# PC3_Output.net
KiCad netlist of a schematic drawn in Altium Designer
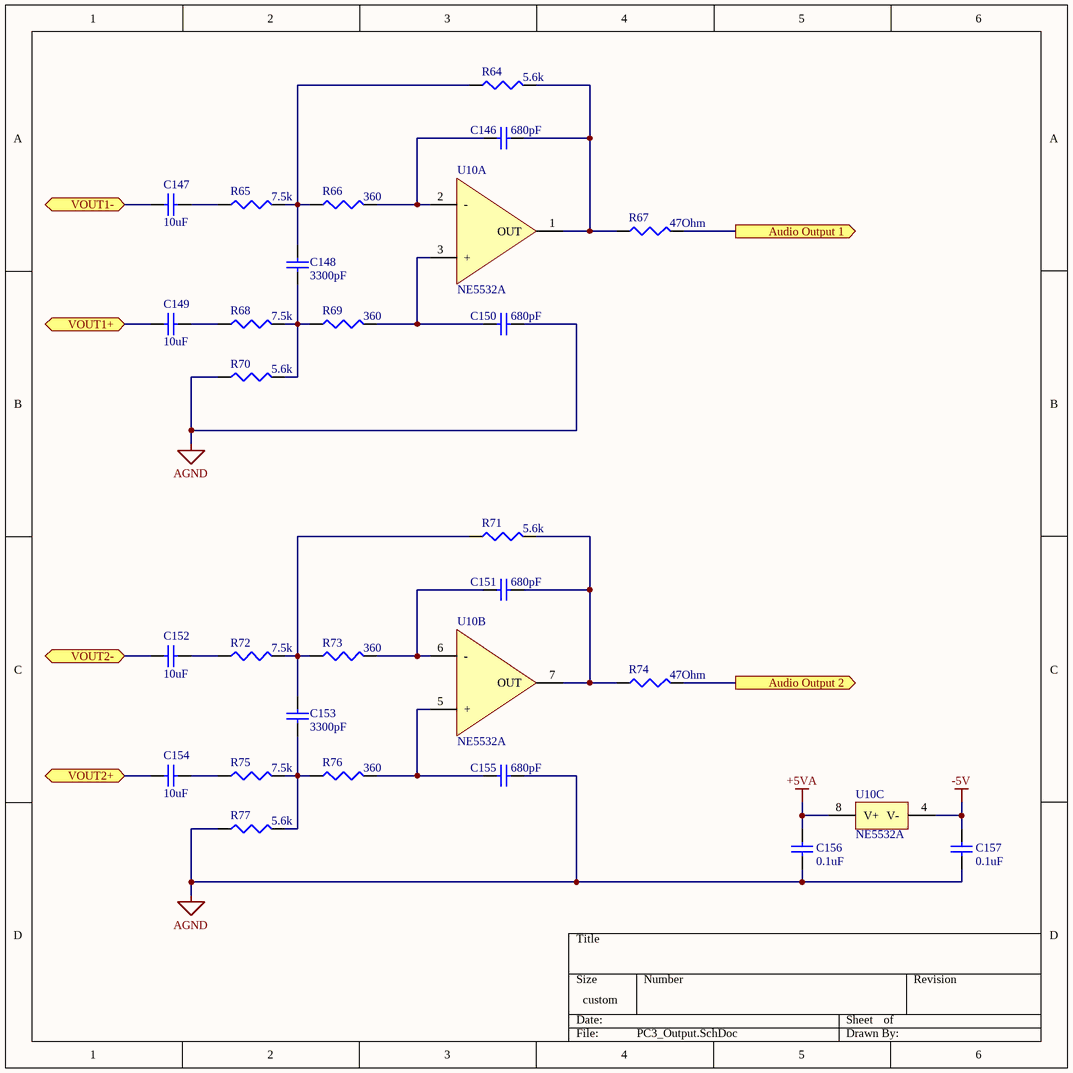
[diagram p0: PC3_Output.SchDoc]

(export (version "E")
  (design (tool "Eeschema 10.0.6"))
  (components
    (comp (ref "C146")
      (value "680pF")
      (footprint "CAPC1608X08")
      (description "Capacitor (Semiconductor SIM Model)")
      (fields (field (name "Comment") "Cap Semi"))
      (libsource (lib "Michel") (part "Cap Semi"))
    )
    (comp (ref "C147")
      (value "10uF")
      (footprint "CAPC1608X08")
      (description "Capacitor (Semiconductor SIM Model)")
      (libsource (lib "Michel") (part "Cap Semi"))
    )
    (comp (ref "C148")
      (value "3300pF")
      (footprint "CAPC1608X08")
      (description "Capacitor (Semiconductor SIM Model)")
      (fields (field (name "Comment") "Cap Semi"))
      (libsource (lib "Michel") (part "Cap Semi"))
    )
    (comp (ref "C149")
      (value "10uF")
      (footprint "CAPC1608X08")
      (description "Capacitor (Semiconductor SIM Model)")
      (libsource (lib "Michel") (part "Cap Semi"))
    )
    (comp (ref "C150")
      (value "680pF")
      (footprint "CAPC1608X08")
      (description "Capacitor (Semiconductor SIM Model)")
      (fields (field (name "Comment") "Cap Semi"))
      (libsource (lib "Michel") (part "Cap Semi"))
    )
    (comp (ref "C151")
      (value "680pF")
      (footprint "CAPC1608X08")
      (description "Capacitor (Semiconductor SIM Model)")
      (fields (field (name "Comment") "Cap Semi"))
      (libsource (lib "Michel") (part "Cap Semi"))
    )
    (comp (ref "C152")
      (value "10uF")
      (footprint "CAPC1608X08")
      (description "Capacitor (Semiconductor SIM Model)")
      (libsource (lib "Michel") (part "Cap Semi"))
    )
    (comp (ref "C153")
      (value "3300pF")
      (footprint "CAPC1608X08")
      (description "Capacitor (Semiconductor SIM Model)")
      (fields (field (name "Comment") "Cap Semi"))
      (libsource (lib "Michel") (part "Cap Semi"))
    )
    (comp (ref "C154")
      (value "10uF")
      (footprint "CAPC1608X08")
      (description "Capacitor (Semiconductor SIM Model)")
      (libsource (lib "Michel") (part "Cap Semi"))
    )
    (comp (ref "C155")
      (value "680pF")
      (footprint "CAPC1608X08")
      (description "Capacitor (Semiconductor SIM Model)")
      (fields (field (name "Comment") "Cap Semi"))
      (libsource (lib "Michel") (part "Cap Semi"))
    )
    (comp (ref "C156")
      (value "0.1uF")
      (footprint "CAPC1608X08")
      (description "Capacitor (Semiconductor SIM Model)")
      (libsource (lib "Michel") (part "Cap Semi"))
    )
    (comp (ref "C157")
      (value "0.1uF")
      (footprint "CAPC1608X08")
      (description "Capacitor (Semiconductor SIM Model)")
      (libsource (lib "Michel") (part "Cap Semi"))
    )
    (comp (ref "R64")
      (value "5.6k")
      (footprint "RESC1608X05")
      (description "Resistor")
      (fields (field (name "Comment") "Res3"))
      (libsource (lib "Michel") (part "Res3"))
    )
    (comp (ref "R65")
      (value "7.5k")
      (footprint "RESC1608X05")
      (description "Resistor")
      (fields (field (name "Comment") "Res3"))
      (libsource (lib "Michel") (part "Res3"))
    )
    (comp (ref "R66")
      (value "360")
      (footprint "RESC1608X05")
      (description "Resistor")
      (fields (field (name "Comment") "Res3"))
      (libsource (lib "Michel") (part "Res3"))
    )
    (comp (ref "R67")
      (value "47Ohm")
      (footprint "RESC1608X05")
      (description "Resistor")
      (fields (field (name "Comment") "Res3"))
      (libsource (lib "Michel") (part "Res3"))
    )
    (comp (ref "R68")
      (value "7.5k")
      (footprint "RESC1608X05")
      (description "Resistor")
      (fields (field (name "Comment") "Res3"))
      (libsource (lib "Michel") (part "Res3"))
    )
    (comp (ref "R69")
      (value "360")
      (footprint "RESC1608X05")
      (description "Resistor")
      (fields (field (name "Comment") "Res3"))
      (libsource (lib "Michel") (part "Res3"))
    )
    (comp (ref "R70")
      (value "5.6k")
      (footprint "RESC1608X05")
      (description "Resistor")
      (fields (field (name "Comment") "Res3"))
      (libsource (lib "Michel") (part "Res3"))
    )
    (comp (ref "R71")
      (value "5.6k")
      (footprint "RESC1608X05")
      (description "Resistor")
      (fields (field (name "Comment") "Res3"))
      (libsource (lib "Michel") (part "Res3"))
    )
    (comp (ref "R72")
      (value "7.5k")
      (footprint "RESC1608X05")
      (description "Resistor")
      (fields (field (name "Comment") "Res3"))
      (libsource (lib "Michel") (part "Res3"))
    )
    (comp (ref "R73")
      (value "360")
      (footprint "RESC1608X05")
      (description "Resistor")
      (fields (field (name "Comment") "Res3"))
      (libsource (lib "Michel") (part "Res3"))
    )
    (comp (ref "R74")
      (value "47Ohm")
      (footprint "RESC1608X05")
      (description "Resistor")
      (fields (field (name "Comment") "Res3"))
      (libsource (lib "Michel") (part "Res3"))
    )
    (comp (ref "R75")
      (value "7.5k")
      (footprint "RESC1608X05")
      (description "Resistor")
      (fields (field (name "Comment") "Res3"))
      (libsource (lib "Michel") (part "Res3"))
    )
    (comp (ref "R76")
      (value "360")
      (footprint "RESC1608X05")
      (description "Resistor")
      (fields (field (name "Comment") "Res3"))
      (libsource (lib "Michel") (part "Res3"))
    )
    (comp (ref "R77")
      (value "5.6k")
      (footprint "RESC1608X05")
      (description "Resistor")
      (fields (field (name "Comment") "Res3"))
      (libsource (lib "Michel") (part "Res3"))
    )
    (comp (ref "U10")
      (value "NE5532A")
      (footprint "D8-M")
      (description "Amplificateur Opérationnel")
      (libsource (lib "Michel") (part "NE5532A"))
    )
  )
  (nets
    (net (code "1") (name "+5VA") (class "Default")
      (node (ref "C156") (pin "1") (pinfunction "1_1") (pintype "passive"))
      (node (ref "U10") (pin "8") (pinfunction "V+_8") (pintype "passive"))
    )
    (net (code "2") (name "-5V") (class "Default")
      (node (ref "C157") (pin "1") (pinfunction "1_1") (pintype "passive"))
      (node (ref "U10") (pin "4") (pinfunction "V-_4") (pintype "passive"))
    )
    (net (code "3") (name "/Audio Output 1") (class "Default")
      (node (ref "R67") (pin "2") (pinfunction "2_2") (pintype "passive"))
    )
    (net (code "4") (name "/Audio Output 2") (class "Default")
      (node (ref "R74") (pin "2") (pinfunction "2_2") (pintype "passive"))
    )
    (net (code "5") (name "/VOUT1+") (class "Default")
      (node (ref "C149") (pin "2") (pinfunction "2_2") (pintype "passive"))
    )
    (net (code "6") (name "/VOUT1-") (class "Default")
      (node (ref "C147") (pin "2") (pinfunction "2_2") (pintype "passive"))
    )
    (net (code "7") (name "/VOUT2+") (class "Default")
      (node (ref "C154") (pin "2") (pinfunction "2_2") (pintype "passive"))
    )
    (net (code "8") (name "/VOUT2-") (class "Default")
      (node (ref "C152") (pin "2") (pinfunction "2_2") (pintype "passive"))
    )
    (net (code "9") (name "AGND") (class "Default")
      (node (ref "C150") (pin "1") (pinfunction "1_1") (pintype "passive"))
      (node (ref "C155") (pin "1") (pinfunction "1_1") (pintype "passive"))
      (node (ref "C156") (pin "2") (pinfunction "2_2") (pintype "passive"))
      (node (ref "C157") (pin "2") (pinfunction "2_2") (pintype "passive"))
      (node (ref "R70") (pin "1") (pinfunction "1_1") (pintype "passive"))
      (node (ref "R77") (pin "1") (pinfunction "1_1") (pintype "passive"))
    )
    (net (code "10") (name "Net-(C147-Pad1)") (class "Default")
      (node (ref "C147") (pin "1") (pinfunction "1_1") (pintype "passive"))
      (node (ref "R65") (pin "1") (pinfunction "1_1") (pintype "passive"))
    )
    (net (code "11") (name "Net-(C148-Pad1)") (class "Default")
      (node (ref "C148") (pin "1") (pinfunction "1_1") (pintype "passive"))
      (node (ref "R64") (pin "1") (pinfunction "1_1") (pintype "passive"))
      (node (ref "R65") (pin "2") (pinfunction "2_2") (pintype "passive"))
      (node (ref "R66") (pin "1") (pinfunction "1_1") (pintype "passive"))
    )
    (net (code "12") (name "Net-(C148-Pad2)") (class "Default")
      (node (ref "C148") (pin "2") (pinfunction "2_2") (pintype "passive"))
      (node (ref "R68") (pin "2") (pinfunction "2_2") (pintype "passive"))
      (node (ref "R69") (pin "1") (pinfunction "1_1") (pintype "passive"))
      (node (ref "R70") (pin "2") (pinfunction "2_2") (pintype "passive"))
    )
    (net (code "13") (name "Net-(C149-Pad1)") (class "Default")
      (node (ref "C149") (pin "1") (pinfunction "1_1") (pintype "passive"))
      (node (ref "R68") (pin "1") (pinfunction "1_1") (pintype "passive"))
    )
    (net (code "14") (name "Net-(C152-Pad1)") (class "Default")
      (node (ref "C152") (pin "1") (pinfunction "1_1") (pintype "passive"))
      (node (ref "R72") (pin "1") (pinfunction "1_1") (pintype "passive"))
    )
    (net (code "15") (name "Net-(C153-Pad1)") (class "Default")
      (node (ref "C153") (pin "1") (pinfunction "1_1") (pintype "passive"))
      (node (ref "R71") (pin "1") (pinfunction "1_1") (pintype "passive"))
      (node (ref "R72") (pin "2") (pinfunction "2_2") (pintype "passive"))
      (node (ref "R73") (pin "1") (pinfunction "1_1") (pintype "passive"))
    )
    (net (code "16") (name "Net-(C153-Pad2)") (class "Default")
      (node (ref "C153") (pin "2") (pinfunction "2_2") (pintype "passive"))
      (node (ref "R75") (pin "2") (pinfunction "2_2") (pintype "passive"))
      (node (ref "R76") (pin "1") (pinfunction "1_1") (pintype "passive"))
      (node (ref "R77") (pin "2") (pinfunction "2_2") (pintype "passive"))
    )
    (net (code "17") (name "Net-(C154-Pad1)") (class "Default")
      (node (ref "C154") (pin "1") (pinfunction "1_1") (pintype "passive"))
      (node (ref "R75") (pin "1") (pinfunction "1_1") (pintype "passive"))
    )
    (net (code "18") (name "Net-(U10A-+)") (class "Default")
      (node (ref "C150") (pin "2") (pinfunction "2_2") (pintype "passive"))
      (node (ref "R69") (pin "2") (pinfunction "2_2") (pintype "passive"))
      (node (ref "U10") (pin "3") (pinfunction "+_3") (pintype "passive"))
    )
    (net (code "19") (name "Net-(U10A--)") (class "Default")
      (node (ref "C146") (pin "2") (pinfunction "2_2") (pintype "passive"))
      (node (ref "R66") (pin "2") (pinfunction "2_2") (pintype "passive"))
      (node (ref "U10") (pin "2") (pinfunction "-_2") (pintype "passive"))
    )
    (net (code "20") (name "Net-(U10A-OUT)") (class "Default")
      (node (ref "C146") (pin "1") (pinfunction "1_1") (pintype "passive"))
      (node (ref "R64") (pin "2") (pinfunction "2_2") (pintype "passive"))
      (node (ref "R67") (pin "1") (pinfunction "1_1") (pintype "passive"))
      (node (ref "U10") (pin "1") (pinfunction "OUT_1") (pintype "passive"))
    )
    (net (code "21") (name "Net-(U10B-+)") (class "Default")
      (node (ref "C155") (pin "2") (pinfunction "2_2") (pintype "passive"))
      (node (ref "R76") (pin "2") (pinfunction "2_2") (pintype "passive"))
      (node (ref "U10") (pin "5") (pinfunction "+_5") (pintype "passive"))
    )
    (net (code "22") (name "Net-(U10B--)") (class "Default")
      (node (ref "C151") (pin "2") (pinfunction "2_2") (pintype "passive"))
      (node (ref "R73") (pin "2") (pinfunction "2_2") (pintype "passive"))
      (node (ref "U10") (pin "6") (pinfunction "-_6") (pintype "passive"))
    )
    (net (code "23") (name "Net-(U10B-OUT)") (class "Default")
      (node (ref "C151") (pin "1") (pinfunction "1_1") (pintype "passive"))
      (node (ref "R71") (pin "2") (pinfunction "2_2") (pintype "passive"))
      (node (ref "R74") (pin "1") (pinfunction "1_1") (pintype "passive"))
      (node (ref "U10") (pin "7") (pinfunction "OUT_7") (pintype "passive"))
    )
  )
)
